# TemperatureSense.net
KiCad netlist of a schematic drawn in Altium Designer
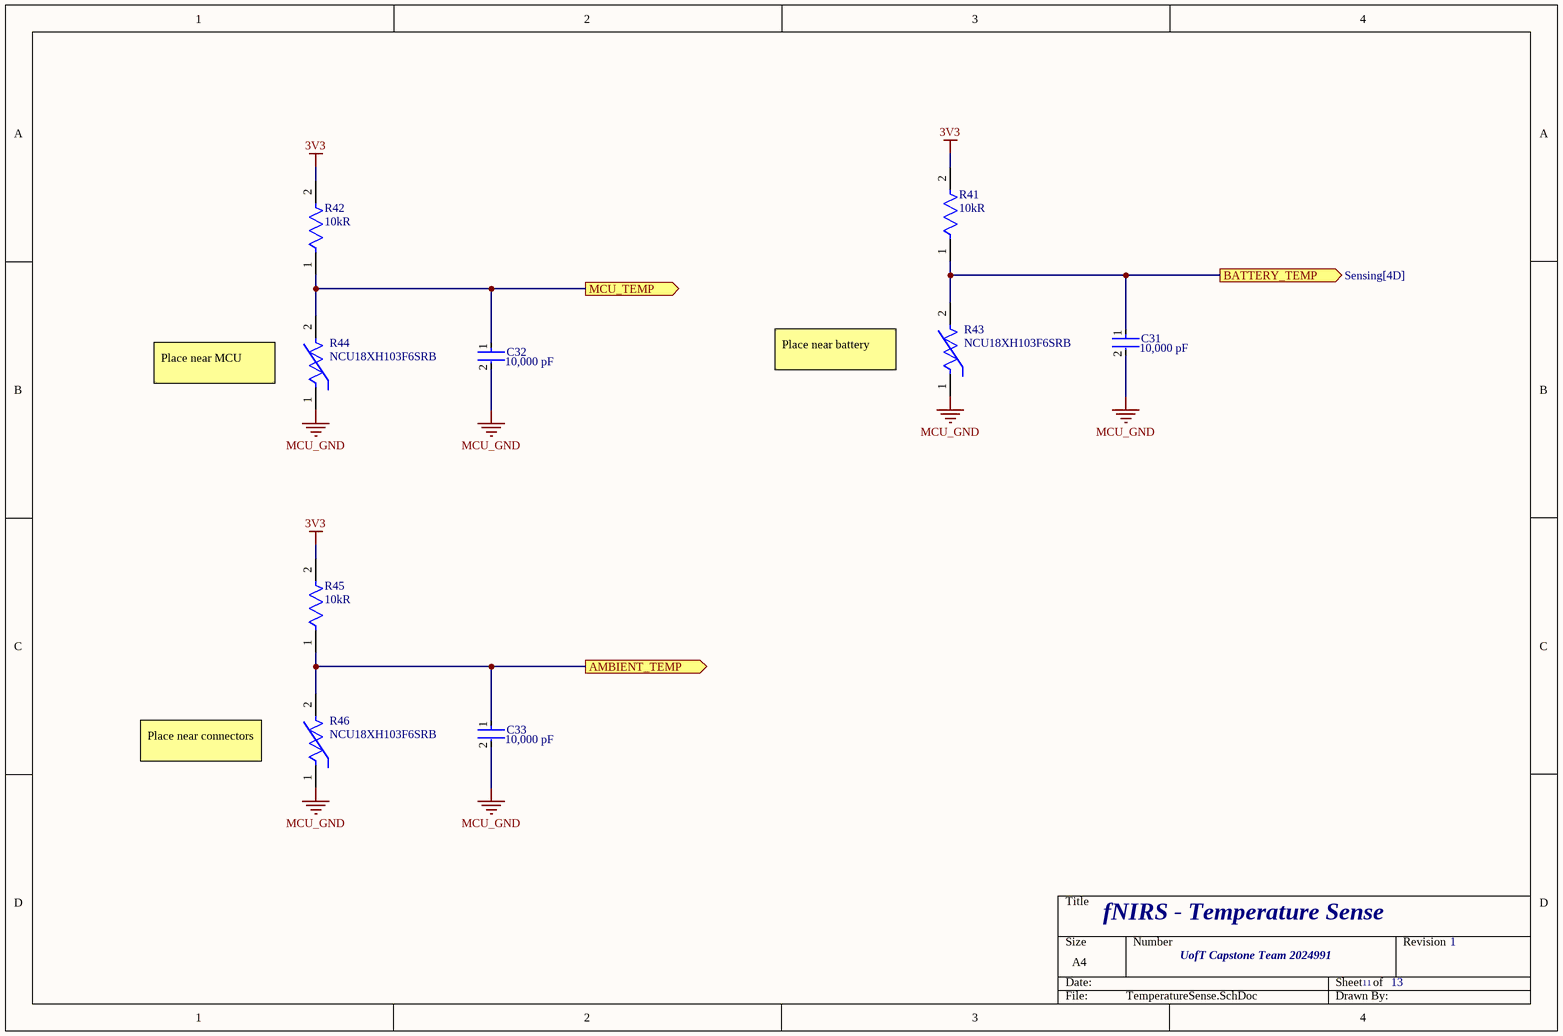
[diagram p0: TemperatureSense.SchDoc]

(export (version "E")
  (design (tool "Eeschema 10.0.6"))
  (components
    (comp (ref "C31")
      (value "C0603C103K2RACTU")
      (footprint "FP-C0603C-CF-MFG")
      (description "CAP CER 10000PF 200V X7R 0603")
      (fields
        (field (name "MANUFACTURER") "KEMET")
        (field (name "OCTOPART") "https://octopart.com/c0603c103k2ractu-kemet-1061947")
        (field (name "CAPACITANCE") "10,000 pF")
      )
      (libsource (lib "Altium Content Vault") (part "b4654b650e69147ec39a6b967a45e02"))
    )
    (comp (ref "C32")
      (value "C0603C103K2RACTU")
      (footprint "FP-C0603C-CF-MFG")
      (description "CAP CER 10000PF 200V X7R 0603")
      (fields
        (field (name "MANUFACTURER") "KEMET")
        (field (name "OCTOPART") "https://octopart.com/c0603c103k2ractu-kemet-1061947")
        (field (name "CAPACITANCE") "10,000 pF")
      )
      (libsource (lib "Altium Content Vault") (part "b4654b650e69147ec39a6b967a45e02"))
    )
    (comp (ref "C33")
      (value "C0603C103K2RACTU")
      (footprint "FP-C0603C-CF-MFG")
      (description "CAP CER 10000PF 200V X7R 0603")
      (fields
        (field (name "MANUFACTURER") "KEMET")
        (field (name "OCTOPART") "https://octopart.com/c0603c103k2ractu-kemet-1061947")
        (field (name "CAPACITANCE") "10,000 pF")
      )
      (libsource (lib "Altium Content Vault") (part "b4654b650e69147ec39a6b967a45e02"))
    )
    (comp (ref "R41")
      (value "CRCW060310K0FKEB")
      (footprint "FP-CRCW0603-e3-IPC_B")
      (description "RES Thick Film, 10kΩ, 1%, 0.1W, 100ppm/°C, 0603")
      (fields (field (name "TOLERANCE") "1%") (field (name "RESISTANCE") "10kR"))
      (libsource (lib "Altium Content Vault") (part "1029c3af85768c4190bb7ad29bc67b5"))
    )
    (comp (ref "R42")
      (value "CRCW060310K0FKEB")
      (footprint "FP-CRCW0603-e3-IPC_B")
      (description "RES Thick Film, 10kΩ, 1%, 0.1W, 100ppm/°C, 0603")
      (fields (field (name "TOLERANCE") "1%") (field (name "RESISTANCE") "10kR"))
      (libsource (lib "Altium Content Vault") (part "1029c3af85768c4190bb7ad29bc67b5"))
    )
    (comp (ref "R43")
      (value "NCU18XH103F6SRB")
      (footprint "FP-NCU18-0_15-IPC_B")
      (description "THERMISTOR NTC")
      (libsource (lib "Altium Content Vault") (part "3b148a6ebabc5fb4d708a66c052d352"))
    )
    (comp (ref "R44")
      (value "NCU18XH103F6SRB")
      (footprint "FP-NCU18-0_15-IPC_B")
      (description "THERMISTOR NTC")
      (libsource (lib "Altium Content Vault") (part "3b148a6ebabc5fb4d708a66c052d352"))
    )
    (comp (ref "R45")
      (value "CRCW060310K0FKEB")
      (footprint "FP-CRCW0603-e3-IPC_B")
      (description "RES Thick Film, 10kΩ, 1%, 0.1W, 100ppm/°C, 0603")
      (fields (field (name "TOLERANCE") "1%") (field (name "RESISTANCE") "10kR"))
      (libsource (lib "Altium Content Vault") (part "1029c3af85768c4190bb7ad29bc67b5"))
    )
    (comp (ref "R46")
      (value "NCU18XH103F6SRB")
      (footprint "FP-NCU18-0_15-IPC_B")
      (description "THERMISTOR NTC")
      (libsource (lib "Altium Content Vault") (part "3b148a6ebabc5fb4d708a66c052d352"))
    )
  )
  (nets
    (net (code "1") (name "/AMBIENT_TEMP") (class "Default")
      (node (ref "C33") (pin "1") (pinfunction "1_1") (pintype "passive"))
      (node (ref "R45") (pin "1") (pinfunction "1_1") (pintype "passive"))
      (node (ref "R46") (pin "2") (pinfunction "2_2") (pintype "passive"))
    )
    (net (code "2") (name "/BATTERY_TEMP") (class "Default")
      (node (ref "C31") (pin "1") (pinfunction "1_1") (pintype "passive"))
      (node (ref "R41") (pin "1") (pinfunction "1_1") (pintype "passive"))
      (node (ref "R43") (pin "2") (pinfunction "2_2") (pintype "passive"))
    )
    (net (code "3") (name "/MCU_TEMP") (class "Default")
      (node (ref "C32") (pin "1") (pinfunction "1_1") (pintype "passive"))
      (node (ref "R42") (pin "1") (pinfunction "1_1") (pintype "passive"))
      (node (ref "R44") (pin "2") (pinfunction "2_2") (pintype "passive"))
    )
    (net (code "4") (name "3V3") (class "Default")
      (node (ref "R41") (pin "2") (pinfunction "2_2") (pintype "passive"))
      (node (ref "R42") (pin "2") (pinfunction "2_2") (pintype "passive"))
      (node (ref "R45") (pin "2") (pinfunction "2_2") (pintype "passive"))
    )
    (net (code "5") (name "MCU_GND") (class "Default")
      (node (ref "C31") (pin "2") (pinfunction "2_2") (pintype "passive"))
      (node (ref "C32") (pin "2") (pinfunction "2_2") (pintype "passive"))
      (node (ref "C33") (pin "2") (pinfunction "2_2") (pintype "passive"))
      (node (ref "R43") (pin "1") (pinfunction "1_1") (pintype "passive"))
      (node (ref "R44") (pin "1") (pinfunction "1_1") (pintype "passive"))
      (node (ref "R46") (pin "1") (pinfunction "1_1") (pintype "passive"))
    )
  )
)
